# SH4_-_IMU.net
KiCad netlist of a schematic drawn in Altium Designer
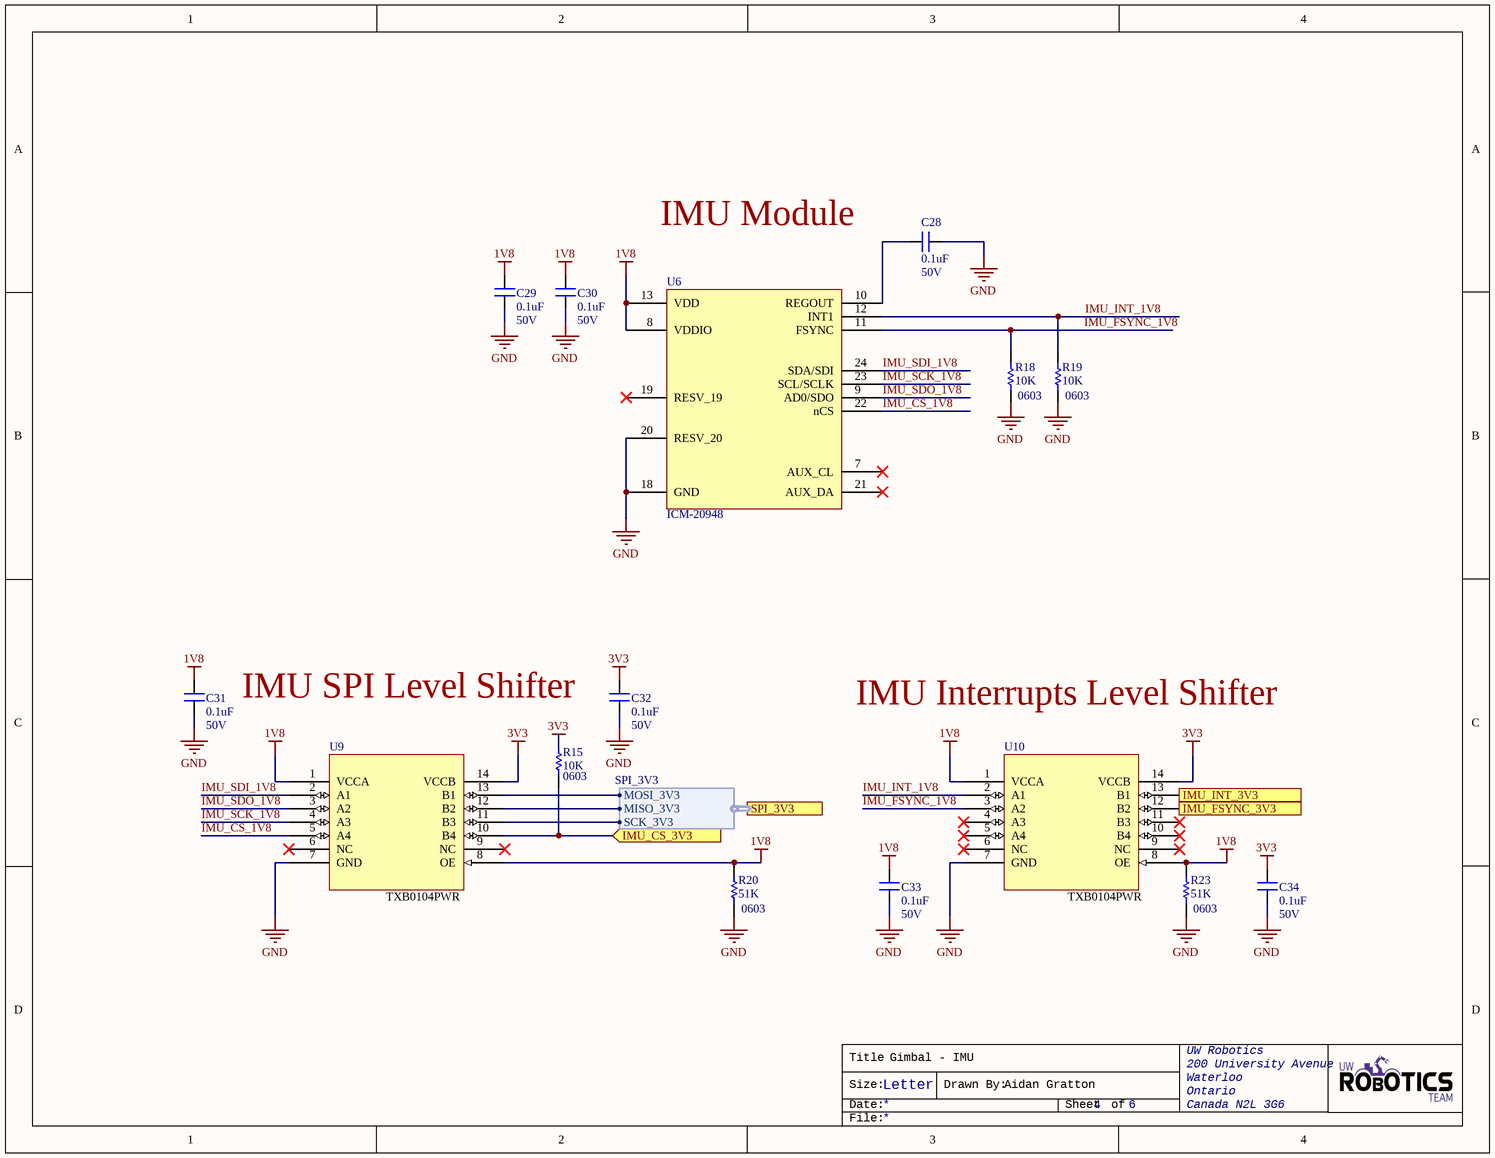
[diagram p0: SH4 - IMU.SchDoc]

(export (version "E")
  (design (tool "Eeschema 10.0.6"))
  (components
    (comp (ref "C28")
      (value "0.1uF")
      (footprint "CAPC2012X140N")
      (description "CAP CER 0.1UF 50V X7R 0805")
      (fields
        (field (name "TOLERANCE") "10%")
        (field (name "VOLTAGE RATING") "50V")
        (field (name "Comment") "CAP_0.1uF_50V_0805")
      )
      (libsource (lib "UWRT_Schematic_Library_2020") (part "CAP_0.1uF_50V_0805"))
    )
    (comp (ref "C29")
      (value "0.1uF")
      (footprint "CAPC2012X140N")
      (description "CAP CER 0.1UF 50V X7R 0805")
      (fields
        (field (name "TOLERANCE") "10%")
        (field (name "VOLTAGE RATING") "50V")
        (field (name "Comment") "CAP_0.1uF_50V_0805")
      )
      (libsource (lib "UWRT_Schematic_Library_2020") (part "CAP_0.1uF_50V_0805"))
    )
    (comp (ref "C30")
      (value "0.1uF")
      (footprint "CAPC2012X140N")
      (description "CAP CER 0.1UF 50V X7R 0805")
      (fields
        (field (name "TOLERANCE") "10%")
        (field (name "VOLTAGE RATING") "50V")
        (field (name "Comment") "CAP_0.1uF_50V_0805")
      )
      (libsource (lib "UWRT_Schematic_Library_2020") (part "CAP_0.1uF_50V_0805"))
    )
    (comp (ref "C31")
      (value "0.1uF")
      (footprint "CAPC2012X140N")
      (description "CAP CER 0.1UF 50V X7R 0805")
      (fields
        (field (name "TOLERANCE") "10%")
        (field (name "VOLTAGE RATING") "50V")
        (field (name "Comment") "CAP_0.1uF_50V_0805")
      )
      (libsource (lib "UWRT_Schematic_Library_2020") (part "CAP_0.1uF_50V_0805"))
    )
    (comp (ref "C32")
      (value "0.1uF")
      (footprint "CAPC2012X140N")
      (description "CAP CER 0.1UF 50V X7R 0805")
      (fields
        (field (name "TOLERANCE") "10%")
        (field (name "VOLTAGE RATING") "50V")
        (field (name "Comment") "CAP_0.1uF_50V_0805")
      )
      (libsource (lib "UWRT_Schematic_Library_2020") (part "CAP_0.1uF_50V_0805"))
    )
    (comp (ref "C33")
      (value "0.1uF")
      (footprint "CAPC2012X140N")
      (description "CAP CER 0.1UF 50V X7R 0805")
      (fields
        (field (name "TOLERANCE") "10%")
        (field (name "VOLTAGE RATING") "50V")
        (field (name "Comment") "CAP_0.1uF_50V_0805")
      )
      (libsource (lib "UWRT_Schematic_Library_2020") (part "CAP_0.1uF_50V_0805"))
    )
    (comp (ref "C34")
      (value "0.1uF")
      (footprint "CAPC2012X140N")
      (description "CAP CER 0.1UF 50V X7R 0805")
      (fields
        (field (name "TOLERANCE") "10%")
        (field (name "VOLTAGE RATING") "50V")
        (field (name "Comment") "CAP_0.1uF_50V_0805")
      )
      (libsource (lib "UWRT_Schematic_Library_2020") (part "CAP_0.1uF_50V_0805"))
    )
    (comp (ref "R15")
      (value "10K")
      (footprint "RESC0603(1608)_N")
      (description "RES SMD 10K OHM 5% 1/10W 0603")
      (fields
        (field (name "PACKAGE") "0603")
        (field (name "MANUFACTURER") "Yageo")
        (field (name "MPN") "RC0603JR-0710KL")
      )
      (libsource (lib "UWRT_Schematic_Library_2020") (part "RES_10K_0603"))
    )
    (comp (ref "R18")
      (value "10K")
      (footprint "RESC0603(1608)_N")
      (description "RES SMD 10K OHM 5% 1/10W 0603")
      (fields
        (field (name "PACKAGE") "0603")
        (field (name "TOLERANCE") "5%")
        (field (name "Comment") "RES_10K_0603")
      )
      (libsource (lib "UWRT_Schematic_Library_2020") (part "RES_10K_0603"))
    )
    (comp (ref "R19")
      (value "10K")
      (footprint "RESC0603(1608)_N")
      (description "RES SMD 10K OHM 5% 1/10W 0603")
      (fields
        (field (name "PACKAGE") "0603")
        (field (name "TOLERANCE") "5%")
        (field (name "Comment") "RES_10K_0603")
      )
      (libsource (lib "UWRT_Schematic_Library_2020") (part "RES_10K_0603"))
    )
    (comp (ref "R20")
      (value "51K")
      (footprint "RESC1608X55N")
      (description "RES SMD 51K OHM 5% 1/10W 0603")
      (fields
        (field (name "PACKAGE") "0603")
        (field (name "TOLERANCE") "5%")
        (field (name "Comment") "RES_51K_0603")
      )
      (libsource (lib "UWRT_Schematic_Library_2020") (part "RES_51K_0603"))
    )
    (comp (ref "R23")
      (value "51K")
      (footprint "RESC1608X55N")
      (description "RES SMD 51K OHM 5% 1/10W 0603")
      (fields
        (field (name "PACKAGE") "0603")
        (field (name "TOLERANCE") "5%")
        (field (name "Comment") "RES_51K_0603")
      )
      (libsource (lib "UWRT_Schematic_Library_2020") (part "RES_51K_0603"))
    )
    (comp (ref "U6")
      (value "IC_9DOF_IMU")
      (footprint "ICM-20948")
      (description "IMU ACCEL/GYRO/COMPI2C/SPI 24QFN")
      (fields
        (field (name "MANUFACTURER") "TDK InvenSense")
        (field (name "MANUFACTURER PART NUMBER") "ICM-20948")
      )
      (libsource (lib "UWRT_Schematic_Library_2020") (part "IC_9DOF_IMU"))
    )
    (comp (ref "U9")
      (value "TXB0104PWR")
      (footprint "UWRT_Footprint_Library_2020:PW14")
      (fields
        (field (name "GENERIC_PART_NUMBER") "TXB0104")
        (field (name "MANUFACTURER PART NUMBER 1") "TXB0104PWR")
      )
      (libsource (lib "UWRT_Schematic_Library_2020") (part "IC_4CH_LVL_SHIFTER"))
    )
    (comp (ref "U10")
      (value "TXB0104PWR")
      (footprint "UWRT_Footprint_Library_2020:PW14")
      (fields
        (field (name "GENERIC_PART_NUMBER") "TXB0104")
        (field (name "MANUFACTURER PART NUMBER 1") "TXB0104PWR")
      )
      (libsource (lib "UWRT_Schematic_Library_2020") (part "IC_4CH_LVL_SHIFTER"))
    )
  )
  (nets
    (net (code "2") (name "/IMU_CS_1V8") (class "Default")
      (node (ref "U6") (pin "22") (pinfunction "nCS_22") (pintype "passive"))
      (node (ref "U9") (pin "5") (pinfunction "A4_5") (pintype "bidirectional"))
    )
    (net (code "3") (name "/IMU_CS_3V3") (class "Default")
      (node (ref "R15") (pin "1") (pinfunction "1_1") (pintype "passive"))
      (node (ref "U9") (pin "10") (pinfunction "B4_10") (pintype "bidirectional"))
    )
    (net (code "4") (name "/IMU_FSYNC_1V8") (class "Default")
      (node (ref "R18") (pin "2") (pinfunction "2_2") (pintype "passive"))
      (node (ref "U10") (pin "3") (pinfunction "A2_3") (pintype "bidirectional"))
      (node (ref "U6") (pin "11") (pinfunction "FSYNC_11") (pintype "passive"))
    )
    (net (code "5") (name "/IMU_FSYNC_3V3") (class "Default")
      (node (ref "U10") (pin "12") (pinfunction "B2_12") (pintype "bidirectional"))
    )
    (net (code "6") (name "/IMU_INT_1V8") (class "Default")
      (node (ref "R19") (pin "2") (pinfunction "2_2") (pintype "passive"))
      (node (ref "U10") (pin "2") (pinfunction "A1_2") (pintype "bidirectional"))
      (node (ref "U6") (pin "12") (pinfunction "INT1_12") (pintype "passive"))
    )
    (net (code "7") (name "/IMU_INT_3V3") (class "Default")
      (node (ref "U10") (pin "13") (pinfunction "B1_13") (pintype "bidirectional"))
    )
    (net (code "8") (name "/IMU_SCK_1V8") (class "Default")
      (node (ref "U6") (pin "23") (pinfunction "SCL/SCLK_23") (pintype "passive"))
      (node (ref "U9") (pin "4") (pinfunction "A3_4") (pintype "bidirectional"))
    )
    (net (code "9") (name "/IMU_SDI_1V8") (class "Default")
      (node (ref "U6") (pin "24") (pinfunction "SDA/SDI_24") (pintype "passive"))
      (node (ref "U9") (pin "2") (pinfunction "A1_2") (pintype "bidirectional"))
    )
    (net (code "10") (name "/IMU_SDO_1V8") (class "Default")
      (node (ref "U6") (pin "9") (pinfunction "AD0/SDO_9") (pintype "passive"))
      (node (ref "U9") (pin "3") (pinfunction "A2_3") (pintype "bidirectional"))
    )
    (net (code "11") (name "/MISO_3V3") (class "Default")
      (node (ref "U9") (pin "12") (pinfunction "B2_12") (pintype "bidirectional"))
    )
    (net (code "12") (name "/MOSI_3V3") (class "Default")
      (node (ref "U9") (pin "13") (pinfunction "B1_13") (pintype "bidirectional"))
    )
    (net (code "13") (name "/SCK_3V3") (class "Default")
      (node (ref "U9") (pin "11") (pinfunction "B3_11") (pintype "bidirectional"))
    )
    (net (code "15") (name "1V8") (class "Default")
      (node (ref "C29") (pin "2") (pinfunction "2_2") (pintype "passive"))
      (node (ref "C30") (pin "2") (pinfunction "2_2") (pintype "passive"))
      (node (ref "C31") (pin "2") (pinfunction "2_2") (pintype "passive"))
      (node (ref "C33") (pin "2") (pinfunction "2_2") (pintype "passive"))
      (node (ref "R20") (pin "2") (pinfunction "2_2") (pintype "passive"))
      (node (ref "R23") (pin "2") (pinfunction "2_2") (pintype "passive"))
      (node (ref "U10") (pin "1") (pinfunction "VCCA_1") (pintype "power_in"))
      (node (ref "U10") (pin "8") (pinfunction "OE_8") (pintype "input"))
      (node (ref "U6") (pin "13") (pinfunction "VDD_13") (pintype "passive"))
      (node (ref "U6") (pin "8") (pinfunction "VDDIO_8") (pintype "passive"))
      (node (ref "U9") (pin "1") (pinfunction "VCCA_1") (pintype "power_in"))
      (node (ref "U9") (pin "8") (pinfunction "OE_8") (pintype "input"))
    )
    (net (code "16") (name "3V3") (class "Default")
      (node (ref "C32") (pin "2") (pinfunction "2_2") (pintype "passive"))
      (node (ref "C34") (pin "2") (pinfunction "2_2") (pintype "passive"))
      (node (ref "R15") (pin "2") (pinfunction "2_2") (pintype "passive"))
      (node (ref "U10") (pin "14") (pinfunction "VCCB_14") (pintype "power_in"))
      (node (ref "U9") (pin "14") (pinfunction "VCCB_14") (pintype "power_in"))
    )
    (net (code "17") (name "GND") (class "Default")
      (node (ref "C28") (pin "2") (pinfunction "2_2") (pintype "passive"))
      (node (ref "C29") (pin "1") (pinfunction "1_1") (pintype "passive"))
      (node (ref "C30") (pin "1") (pinfunction "1_1") (pintype "passive"))
      (node (ref "C31") (pin "1") (pinfunction "1_1") (pintype "passive"))
      (node (ref "C32") (pin "1") (pinfunction "1_1") (pintype "passive"))
      (node (ref "C33") (pin "1") (pinfunction "1_1") (pintype "passive"))
      (node (ref "C34") (pin "1") (pinfunction "1_1") (pintype "passive"))
      (node (ref "R18") (pin "1") (pinfunction "1_1") (pintype "passive"))
      (node (ref "R19") (pin "1") (pinfunction "1_1") (pintype "passive"))
      (node (ref "R20") (pin "1") (pinfunction "1_1") (pintype "passive"))
      (node (ref "R23") (pin "1") (pinfunction "1_1") (pintype "passive"))
      (node (ref "U10") (pin "7") (pinfunction "GND_7") (pintype "power_in"))
      (node (ref "U6") (pin "18") (pinfunction "GND_18") (pintype "passive"))
      (node (ref "U6") (pin "20") (pinfunction "RESV_20_20") (pintype "passive"))
      (node (ref "U9") (pin "7") (pinfunction "GND_7") (pintype "power_in"))
    )
    (net (code "18") (name "Net-(U6-REGOUT)") (class "Default")
      (node (ref "C28") (pin "1") (pinfunction "1_1") (pintype "passive"))
      (node (ref "U6") (pin "10") (pinfunction "REGOUT_10") (pintype "passive"))
    )
    (net (code "19") (name "unconnected-(U6-AUX_CL-Pad7)") (class "Default")
      (node (ref "U6") (pin "7") (pinfunction "AUX_CL_7") (pintype "passive+no_connect"))
    )
    (net (code "20") (name "unconnected-(U6-AUX_DA-Pad21)") (class "Default")
      (node (ref "U6") (pin "21") (pinfunction "AUX_DA_21") (pintype "passive+no_connect"))
    )
    (net (code "21") (name "unconnected-(U6-RESV_19-Pad19)") (class "Default")
      (node (ref "U6") (pin "19") (pinfunction "RESV_19_19") (pintype "passive+no_connect"))
    )
    (net (code "22") (name "unconnected-(U9-NC-Pad6)") (class "Default")
      (node (ref "U9") (pin "6") (pinfunction "NC_6") (pintype "passive+no_connect"))
    )
    (net (code "23") (name "unconnected-(U9-NC-Pad9)") (class "Default")
      (node (ref "U9") (pin "9") (pinfunction "NC_9") (pintype "passive+no_connect"))
    )
    (net (code "24") (name "unconnected-(U10-A3-Pad4)") (class "Default")
      (node (ref "U10") (pin "4") (pinfunction "A3_4") (pintype "bidirectional+no_connect"))
    )
    (net (code "25") (name "unconnected-(U10-A4-Pad5)") (class "Default")
      (node (ref "U10") (pin "5") (pinfunction "A4_5") (pintype "bidirectional+no_connect"))
    )
    (net (code "26") (name "unconnected-(U10-B3-Pad11)") (class "Default")
      (node (ref "U10") (pin "11") (pinfunction "B3_11") (pintype "bidirectional+no_connect"))
    )
    (net (code "27") (name "unconnected-(U10-B4-Pad10)") (class "Default")
      (node (ref "U10") (pin "10") (pinfunction "B4_10") (pintype "bidirectional+no_connect"))
    )
    (net (code "28") (name "unconnected-(U10-NC-Pad6)") (class "Default")
      (node (ref "U10") (pin "6") (pinfunction "NC_6") (pintype "passive+no_connect"))
    )
    (net (code "29") (name "unconnected-(U10-NC-Pad9)") (class "Default")
      (node (ref "U10") (pin "9") (pinfunction "NC_9") (pintype "passive+no_connect"))
    )
  )
)
